# Fleet-Monitor-CAN.net
KiCad netlist of a schematic drawn in Altium Designer
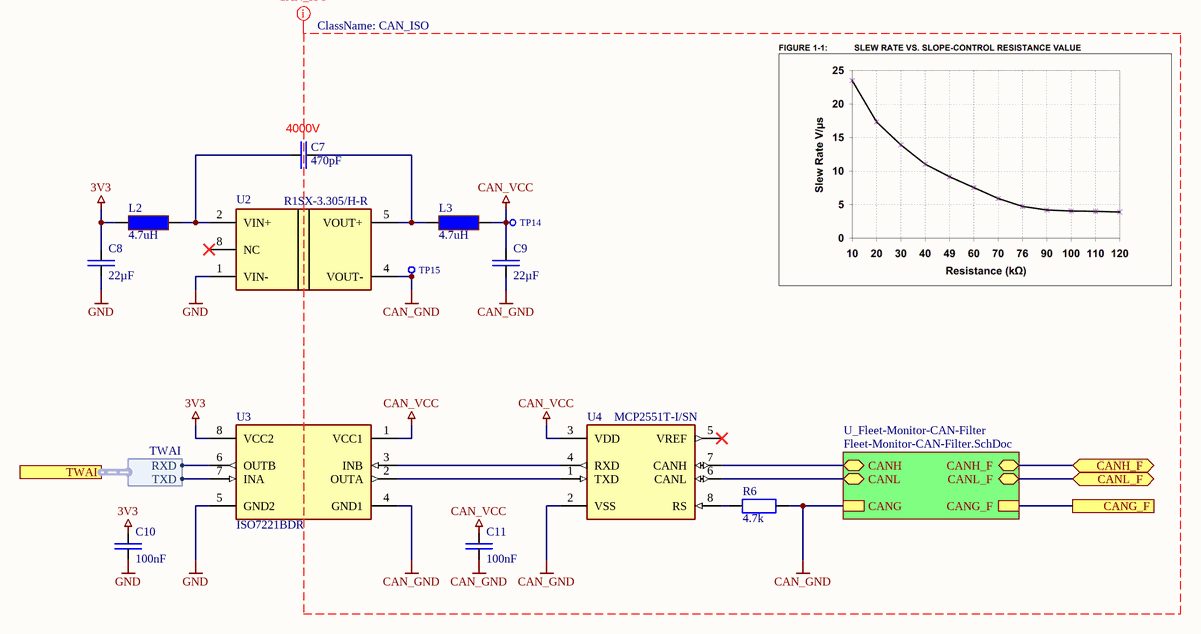
[diagram p0: Fleet-Monitor-CAN.SchDoc]

(export (version "E")
  (design (tool "Eeschema 10.0.6"))
  (components
    (comp (ref "C7")
      (value "470pF")
      (footprint "SMD Keramikkondensator 1808")
      (description "SMD Ceramic Capacitor E6")
      (libsource (lib "Ceramic Capacitors-E6") (part "E6 - 470pF"))
    )
    (comp (ref "C8")
      (value "22µF")
      (footprint "SMD Keramikkondensator 0603")
      (description "SMD Ceramic Capacitor E6")
      (libsource (lib "Ceramic Capacitors-E6") (part "E6 - 22uF"))
    )
    (comp (ref "C9")
      (value "22µF")
      (footprint "SMD Keramikkondensator 0603")
      (description "SMD Ceramic Capacitor E6")
      (libsource (lib "Ceramic Capacitors-E6") (part "E6 - 22uF"))
    )
    (comp (ref "C10")
      (value "100nF")
      (footprint "SMD Keramikkondensator 0603")
      (description "SMD Ceramic Capacitor E6")
      (libsource (lib "Ceramic Capacitors-E6") (part "E6 - 100nF"))
    )
    (comp (ref "C11")
      (value "100nF")
      (footprint "SMD Keramikkondensator 0603")
      (description "SMD Ceramic Capacitor E6")
      (libsource (lib "Ceramic Capacitors-E6") (part "E6 - 100nF"))
    )
    (comp (ref "L2")
      (value "4.7uH")
      (footprint "SMD INDUCTOR/FERRITE 0805")
      (description "0805 Inductor 4.7uH")
      (libsource (lib "Inductors") (part "MLP2012V4R7MT0S1"))
    )
    (comp (ref "L3")
      (value "4.7uH")
      (footprint "SMD INDUCTOR/FERRITE 0805")
      (description "0805 Inductor 4.7uH")
      (libsource (lib "Inductors") (part "MLP2012V4R7MT0S1"))
    )
    (comp (ref "R6")
      (value "4.7k")
      (footprint "SMD Widerstand 0603")
      (description "SMD Chip Resistor E24")
      (libsource (lib "Fleet-Monitor") (part "E24 - 4.7k"))
    )
    (comp (ref "TP14")
      (value "X-TP")
      (footprint "SMD Testpunkt Ø1mm")
      (description "Testpunkt")
      (libsource (lib "VLD-Monitor_V1.0") (part "X-TP"))
    )
    (comp (ref "TP15")
      (value "X-TP")
      (footprint "SMD Testpunkt Ø1mm")
      (description "Testpunkt")
      (libsource (lib "VLD-Monitor_V1.0") (part "X-TP"))
    )
    (comp (ref "U2")
      (value "R1SX-3.305/H-R")
      (footprint "SMD DCDC R1SX")
      (description "Isolated Module DC DC Converter 1 Output 5V - - - 200mA 2.97V - 3.63V Input")
      (libsource (lib "Fleet-Monitor") (part "R1SX-3.305/H-R"))
    )
    (comp (ref "U3")
      (value "ISO7221BDR")
      (footprint "SMD IC SOIC-8")
      (libsource (lib "Fleet-Monitor") (part "ISO7221BDR"))
    )
    (comp (ref "U4")
      (value "MCP2551T-I/SN")
      (footprint "SMD IC SOIC-8")
      (description "High-Speed CAN Transceiver")
      (libsource (lib "Fleet-Monitor") (part "MCP2551T-I/SN"))
    )
  )
  (nets
    (net (code "3") (name "/CANH") (class "Default")
      (node (ref "U4") (pin "7") (pinfunction "CANH_7") (pintype "bidirectional"))
    )
    (net (code "5") (name "/CANL") (class "Default")
      (node (ref "U4") (pin "6") (pinfunction "CANL_6") (pintype "bidirectional"))
    )
    (net (code "7") (name "/RXD") (class "Default")
      (node (ref "U3") (pin "6") (pinfunction "OUTB_6") (pintype "output"))
    )
    (net (code "8") (name "/TXD") (class "Default")
      (node (ref "U3") (pin "7") (pinfunction "INA_7") (pintype "input"))
    )
    (net (code "10") (name "3V3") (class "Default")
      (node (ref "C10") (pin "2") (pinfunction "2_2") (pintype "passive"))
      (node (ref "C8") (pin "2") (pinfunction "2_2") (pintype "passive"))
      (node (ref "L2") (pin "1") (pinfunction "1_1") (pintype "passive"))
      (node (ref "U3") (pin "8") (pinfunction "VCC2_8") (pintype "passive"))
    )
    (net (code "11") (name "CAN_GND") (class "Default")
      (node (ref "C11") (pin "1") (pinfunction "1_1") (pintype "passive"))
      (node (ref "C9") (pin "1") (pinfunction "1_1") (pintype "passive"))
      (node (ref "R6") (pin "2") (pinfunction "2_2") (pintype "passive"))
      (node (ref "TP15") (pin "1") (pinfunction "1_1") (pintype "passive"))
      (node (ref "U2") (pin "4") (pinfunction "VOUT-_4") (pintype "passive"))
      (node (ref "U3") (pin "4") (pinfunction "GND1_4") (pintype "passive"))
      (node (ref "U4") (pin "2") (pinfunction "VSS_2") (pintype "passive"))
    )
    (net (code "12") (name "CAN_VCC") (class "Default")
      (node (ref "C11") (pin "2") (pinfunction "2_2") (pintype "passive"))
      (node (ref "C9") (pin "2") (pinfunction "2_2") (pintype "passive"))
      (node (ref "L3") (pin "2") (pinfunction "2_2") (pintype "passive"))
      (node (ref "TP14") (pin "1") (pinfunction "1_1") (pintype "passive"))
      (node (ref "U3") (pin "1") (pinfunction "VCC1_1") (pintype "passive"))
      (node (ref "U4") (pin "3") (pinfunction "VDD_3") (pintype "passive"))
    )
    (net (code "13") (name "GND") (class "Default")
      (node (ref "C10") (pin "1") (pinfunction "1_1") (pintype "passive"))
      (node (ref "C8") (pin "1") (pinfunction "1_1") (pintype "passive"))
      (node (ref "U2") (pin "1") (pinfunction "VIN-_1") (pintype "passive"))
      (node (ref "U3") (pin "5") (pinfunction "GND2_5") (pintype "passive"))
    )
    (net (code "14") (name "Net-(U2-VIN+)") (class "Default")
      (node (ref "C7") (pin "1") (pinfunction "1_1") (pintype "passive"))
      (node (ref "L2") (pin "2") (pinfunction "2_2") (pintype "passive"))
      (node (ref "U2") (pin "2") (pinfunction "VIN+_2") (pintype "passive"))
    )
    (net (code "15") (name "Net-(U2-VOUT+)") (class "Default")
      (node (ref "C7") (pin "2") (pinfunction "2_2") (pintype "passive"))
      (node (ref "L3") (pin "1") (pinfunction "1_1") (pintype "passive"))
      (node (ref "U2") (pin "5") (pinfunction "VOUT+_5") (pintype "passive"))
    )
    (net (code "16") (name "Net-(U3-INB)") (class "Default")
      (node (ref "U3") (pin "3") (pinfunction "INB_3") (pintype "input"))
      (node (ref "U4") (pin "4") (pinfunction "RXD_4") (pintype "output"))
    )
    (net (code "17") (name "Net-(U3-OUTA)") (class "Default")
      (node (ref "U3") (pin "2") (pinfunction "OUTA_2") (pintype "output"))
      (node (ref "U4") (pin "1") (pinfunction "TXD_1") (pintype "input"))
    )
    (net (code "18") (name "Net-(U4-RS)") (class "Default")
      (node (ref "R6") (pin "1") (pinfunction "1_1") (pintype "passive"))
      (node (ref "U4") (pin "8") (pinfunction "RS_8") (pintype "input"))
    )
    (net (code "19") (name "unconnected-(U2-NC-Pad8)") (class "Default")
      (node (ref "U2") (pin "8") (pinfunction "NC_8") (pintype "passive+no_connect"))
    )
    (net (code "20") (name "unconnected-(U4-VREF-Pad5)") (class "Default")
      (node (ref "U4") (pin "5") (pinfunction "VREF_5") (pintype "output+no_connect"))
    )
  )
)
